# design.net
KiCad netlist of a schematic drawn in Altium Designer
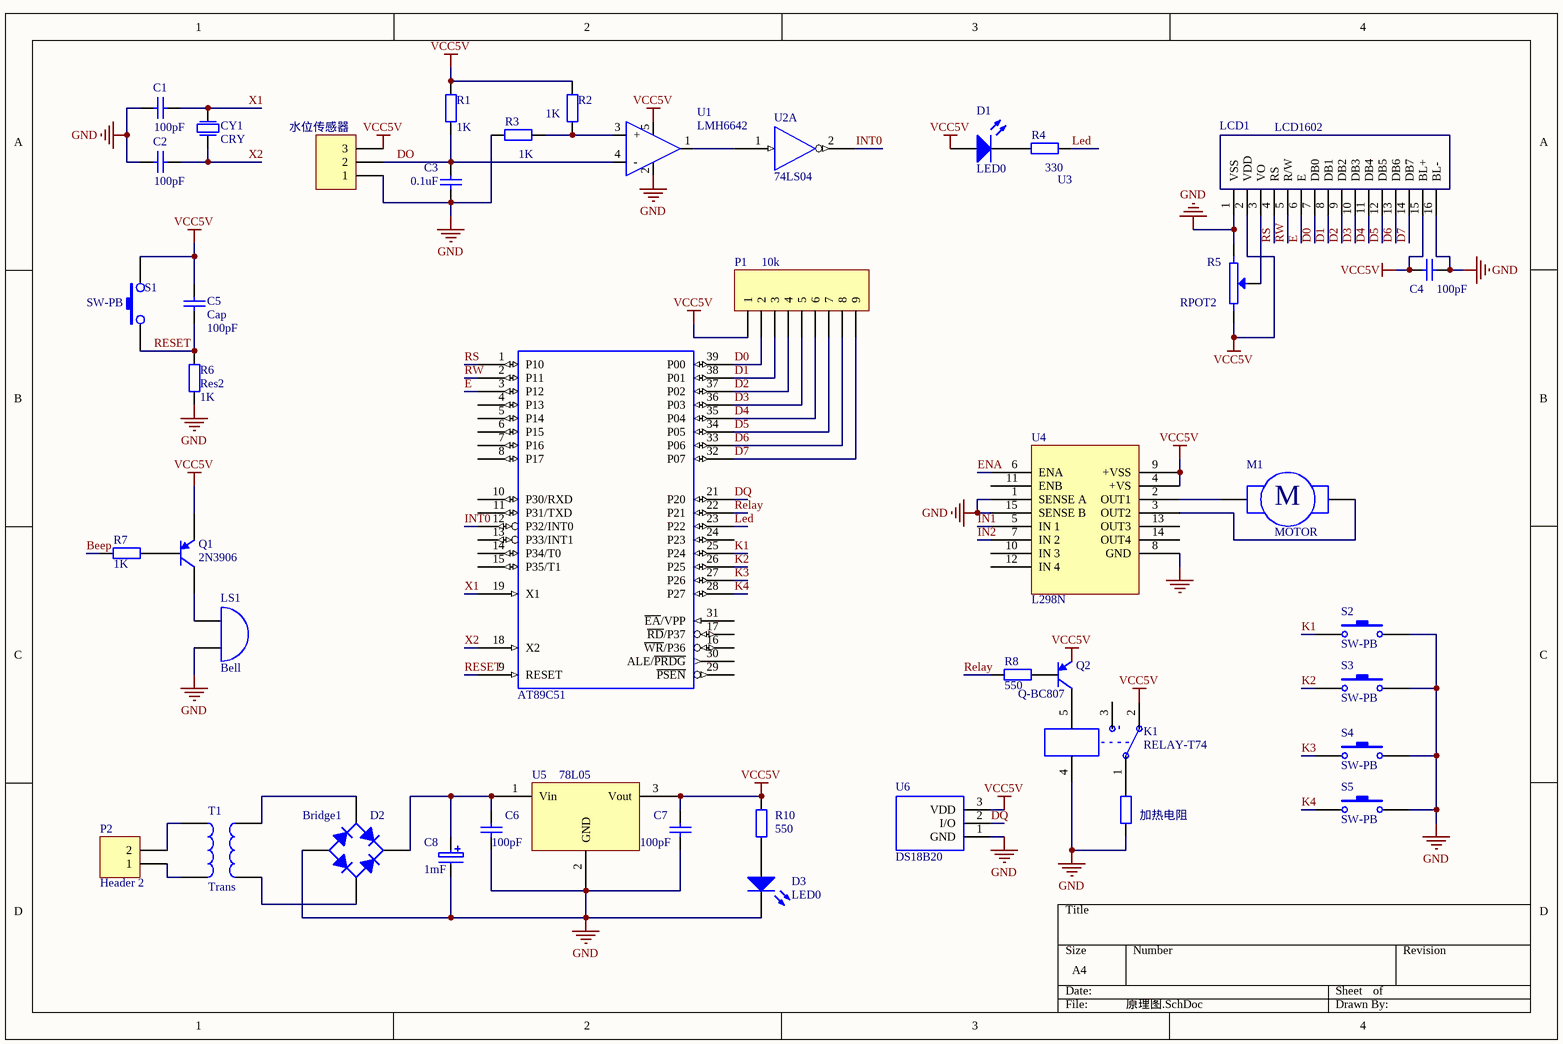
[diagram p0: 原理图.SchDoc]

(export (version "E")
  (design (tool "Eeschema 10.0.6"))
  (components
    (comp (ref "C1")
      (value "100pF")
      (footprint "RAD-0.3")
      (description "Capacitor")
      (fields (field (name "Comment") "Cap") (field (name "PUBLISHER") "Altium Limited"))
      (libsource (lib "Miscellaneous Devices") (part "Cap"))
    )
    (comp (ref "C2")
      (value "100pF")
      (footprint "RAD-0.3")
      (description "Capacitor")
      (fields (field (name "Comment") "Cap") (field (name "PUBLISHER") "Altium Limited"))
      (libsource (lib "Miscellaneous Devices") (part "Cap"))
    )
    (comp (ref "C3")
      (value "0.1uF")
      (footprint "RAD-0.3")
      (description "Capacitor")
      (fields (field (name "Comment") "Cap") (field (name "PUBLISHER") "Altium Limited"))
      (libsource (lib "Miscellaneous Devices") (part "Cap"))
    )
    (comp (ref "C4")
      (value "100pF")
      (footprint "RAD-0.3")
      (description "Capacitor")
      (fields (field (name "Comment") "Cap") (field (name "PUBLISHER") "Altium Limited"))
      (libsource (lib "Miscellaneous Devices") (part "Cap"))
    )
    (comp (ref "C5")
      (value "Cap")
      (footprint "RAD-0.3")
      (description "Capacitor")
      (fields (field (name "ALTIUM_VALUE") "100pF") (field (name "PUBLISHER") "Altium Limited"))
      (libsource (lib "Miscellaneous Devices") (part "Cap"))
    )
    (comp (ref "C6")
      (value "100pF")
      (footprint "RAD-0.3")
      (description "Capacitor")
      (fields (field (name "Comment") "Cap") (field (name "PUBLISHER") "Altium Limited"))
      (libsource (lib "Miscellaneous Devices") (part "Cap"))
    )
    (comp (ref "C7")
      (value "100pF")
      (footprint "RAD-0.3")
      (description "Capacitor")
      (fields (field (name "Comment") "Cap") (field (name "PUBLISHER") "Altium Limited"))
      (libsource (lib "Miscellaneous Devices") (part "Cap"))
    )
    (comp (ref "C8") (value "1mF") (footprint "RB1") (libsource (lib "C电容") (part "CAP3")))
    (comp (ref "CY1") (value "CRY") (footprint "XTAL-1") (libsource (lib "CRY晶振") (part "CRY")))
    (comp (ref "D1")
      (value "LED0")
      (footprint "LED-0")
      (description "Typical INFRARED GaAs LED")
      (fields (field (name "PUBLISHER") "Altium Limited"))
      (libsource (lib "Miscellaneous Devices") (part "LED0"))
    )
    (comp (ref "D2")
      (value "Bridge1")
      (footprint "D-38")
      (description "Full Wave Diode Bridge")
      (fields (field (name "PUBLISHER") "Altium Limited"))
      (libsource (lib "Miscellaneous Devices") (part "Bridge1"))
    )
    (comp (ref "D3")
      (value "LED0")
      (footprint "LED-0")
      (description "Typical INFRARED GaAs LED")
      (fields (field (name "PUBLISHER") "Altium Limited"))
      (libsource (lib "Miscellaneous Devices") (part "LED0"))
    )
    (comp (ref "K1")
      (value "RELAY-T74")
      (footprint "RELAY-T74")
      (description "CN-RELAY-T74")
      (libsource (lib "常用器件") (part "RELAY-T74"))
    )
    (comp (ref "LCD1") (value "LCD1602") (footprint "LCD1602") (libsource (lib "LCD1602") (part "LCD1602")))
    (comp (ref "LS1")
      (value "Bell")
      (footprint "PIN2")
      (description "Electrical Bell")
      (fields (field (name "PUBLISHER") "Altium Limited"))
      (libsource (lib "Miscellaneous Devices") (part "Bell"))
    )
    (comp (ref "M1") (value "MOTOR") (footprint "DG1282") (libsource (lib "单片机及相关") (part "MOTOR")))
    (comp (ref "P1")
      (value "10k")
      (footprint "MHDR1X9")
      (description "Header, 9-Pin")
      (fields (field (name "PUBLISHER") "Altium Limited"))
      (libsource (lib "Miscellaneous Connectors") (part "MHDR1X9"))
    )
    (comp (ref "P2")
      (value "Header 2")
      (footprint "HDR1X2")
      (description "Header, 2-Pin")
      (fields (field (name "PUBLISHER") "Altium Limited"))
      (libsource (lib "Miscellaneous Connectors") (part "Header 2"))
    )
    (comp (ref "Q1")
      (value "2N3906")
      (footprint "TO-92A")
      (description "PNP General Purpose Amplifier")
      (fields (field (name "PUBLISHER") "Altium Limited"))
      (libsource (lib "Miscellaneous Devices") (part "2N3906"))
    )
    (comp (ref "Q2")
      (value "Q-BC807")
      (footprint "SOT-23Q")
      (description "PNP General Purpose Amplifier")
      (fields (field (name "PUBLISHER") "Altium Limited"))
      (libsource (lib "常用器件") (part "Q-BC807"))
    )
    (comp (ref "R1")
      (value "1K")
      (footprint "AXIAL-0.4")
      (description "Resistor")
      (fields (field (name "Comment") "Res2") (field (name "PUBLISHER") "Altium Limited"))
      (libsource (lib "") (part "Res2_1"))
    )
    (comp (ref "R2")
      (value "1K")
      (footprint "AXIAL-0.4")
      (description "Resistor")
      (fields (field (name "Comment") "Res2") (field (name "PUBLISHER") "Altium Limited"))
      (libsource (lib "") (part "Res2_1"))
    )
    (comp (ref "R3")
      (value "1K")
      (footprint "AXIAL-0.4")
      (description "Resistor")
      (fields (field (name "Comment") "Res2") (field (name "PUBLISHER") "Altium Limited"))
      (libsource (lib "Miscellaneous Devices") (part "Res2"))
    )
    (comp (ref "R4")
      (value "330")
      (footprint "AXIAL-0.4")
      (description "Resistor")
      (fields (field (name "Comment") "Res2") (field (name "PUBLISHER") "Altium Limited"))
      (libsource (lib "Miscellaneous Devices") (part "Res2"))
    )
    (comp (ref "R5")
      (value "RPOT2")
      (footprint "VR5")
      (description "Potentiometer")
      (libsource (lib "电阻") (part "RPOT2"))
    )
    (comp (ref "R6")
      (value "Res2")
      (footprint "AXIAL-0.4")
      (description "Resistor")
      (fields (field (name "ALTIUM_VALUE") "1K") (field (name "PUBLISHER") "Altium Limited"))
      (libsource (lib "") (part "Res2_1"))
    )
    (comp (ref "R7")
      (value "1K")
      (footprint "AXIAL-0.4")
      (description "Resistor")
      (fields (field (name "Comment") "Res2") (field (name "PUBLISHER") "Altium Limited"))
      (libsource (lib "Miscellaneous Devices") (part "Res2"))
    )
    (comp (ref "R8")
      (value "550")
      (footprint "AXIAL-0.4")
      (description "Resistor")
      (fields (field (name "Comment") "Res2") (field (name "PUBLISHER") "Altium Limited"))
      (libsource (lib "Miscellaneous Devices") (part "Res2"))
    )
    (comp (ref "R10")
      (value "550")
      (footprint "AXIAL-0.4")
      (description "Resistor")
      (fields (field (name "Comment") "Res2") (field (name "PUBLISHER") "Altium Limited"))
      (libsource (lib "") (part "Res2_1"))
    )
    (comp (ref "S1") (value "SW-PB") (libsource (lib "SW开关") (part "SW-PB")))
    (comp (ref "S2")
      (value "SW-PB")
      (footprint "SPST-2")
      (description "Switch")
      (fields (field (name "PUBLISHER") "Altium Limited"))
      (libsource (lib "常用器件") (part "SW-PB"))
    )
    (comp (ref "S3")
      (value "SW-PB")
      (footprint "SPST-2")
      (description "Switch")
      (fields (field (name "PUBLISHER") "Altium Limited"))
      (libsource (lib "常用器件") (part "SW-PB"))
    )
    (comp (ref "S4")
      (value "SW-PB")
      (footprint "SPST-2")
      (description "Switch")
      (fields (field (name "PUBLISHER") "Altium Limited"))
      (libsource (lib "常用器件") (part "SW-PB"))
    )
    (comp (ref "S5")
      (value "SW-PB")
      (footprint "SPST-2")
      (description "Switch")
      (fields (field (name "PUBLISHER") "Altium Limited"))
      (libsource (lib "常用器件") (part "SW-PB"))
    )
    (comp (ref "T1")
      (value "Trans")
      (footprint "TRANS")
      (description "Transformer")
      (fields (field (name "PUBLISHER") "Altium Limited"))
      (libsource (lib "Miscellaneous Devices") (part "Trans"))
    )
    (comp (ref "U1") (value "LMH6642") (description "Amplifier IC") (libsource (lib "常用器件") (part "LMH6642")))
    (comp (ref "U2") (value "74LS04") (footprint "DIP-14") (libsource (lib "74xxTTL") (part "74LS04")))
    (comp (ref "U3") (value "AT89C51") (footprint "DIP-40") (libsource (lib "单片机及相关") (part "AT89C51")))
    (comp (ref "U4") (value "L298N") (footprint "L298N散热片") (libsource (lib "KU1") (part "L298N")))
    (comp (ref "U5") (value "78L05") (footprint "TO257V") (libsource (lib "稳压管") (part "78**")))
    (comp (ref "U6") (value "DS18B20") (footprint "TO-92A") (libsource (lib "单片机及相关") (part "DS18B20")))
    (comp (ref "加热电阻")
      (value "Res2")
      (footprint "AXIAL-0.4")
      (description "Resistor")
      (fields (field (name "PUBLISHER") "Altium Limited"))
      (libsource (lib "") (part "Res2_1"))
    )
    (comp (ref "水位传感器")
      (value "Header 3H")
      (footprint "HDR1X3H")
      (description "Header, 3-Pin, Right Angle")
      (fields (field (name "PUBLISHER") "Altium Limited"))
      (libsource (lib "Miscellaneous Connectors") (part "Header 3H"))
    )
  )
  (nets
    (net (code "1") (name "/Beep") (class "Default")
      (node (ref "R7") (pin "2") (pinfunction "2_2") (pintype "passive"))
    )
    (net (code "2") (name "/D0") (class "Default")
      (node (ref "LCD1") (pin "7") (pinfunction "DB0_7") (pintype "passive"))
      (node (ref "P1") (pin "2") (pinfunction "2_2") (pintype "passive"))
      (node (ref "U3") (pin "39") (pinfunction "P00_39") (pintype "bidirectional"))
    )
    (net (code "3") (name "/D1") (class "Default")
      (node (ref "LCD1") (pin "8") (pinfunction "DB1_8") (pintype "passive"))
      (node (ref "P1") (pin "3") (pinfunction "3_3") (pintype "passive"))
      (node (ref "U3") (pin "38") (pinfunction "P01_38") (pintype "bidirectional"))
    )
    (net (code "4") (name "/D2") (class "Default")
      (node (ref "LCD1") (pin "9") (pinfunction "DB2_9") (pintype "passive"))
      (node (ref "P1") (pin "4") (pinfunction "4_4") (pintype "passive"))
      (node (ref "U3") (pin "37") (pinfunction "P02_37") (pintype "bidirectional"))
    )
    (net (code "5") (name "/D3") (class "Default")
      (node (ref "LCD1") (pin "10") (pinfunction "DB3_10") (pintype "passive"))
      (node (ref "P1") (pin "5") (pinfunction "5_5") (pintype "passive"))
      (node (ref "U3") (pin "36") (pinfunction "P03_36") (pintype "bidirectional"))
    )
    (net (code "6") (name "/D4") (class "Default")
      (node (ref "LCD1") (pin "11") (pinfunction "DB4_11") (pintype "passive"))
      (node (ref "P1") (pin "6") (pinfunction "6_6") (pintype "passive"))
      (node (ref "U3") (pin "35") (pinfunction "P04_35") (pintype "bidirectional"))
    )
    (net (code "7") (name "/D5") (class "Default")
      (node (ref "LCD1") (pin "12") (pinfunction "DB5_12") (pintype "passive"))
      (node (ref "P1") (pin "7") (pinfunction "7_7") (pintype "passive"))
      (node (ref "U3") (pin "34") (pinfunction "P05_34") (pintype "bidirectional"))
    )
    (net (code "8") (name "/D6") (class "Default")
      (node (ref "LCD1") (pin "13") (pinfunction "DB6_13") (pintype "passive"))
      (node (ref "P1") (pin "8") (pinfunction "8_8") (pintype "passive"))
      (node (ref "U3") (pin "33") (pinfunction "P06_33") (pintype "bidirectional"))
    )
    (net (code "9") (name "/D7") (class "Default")
      (node (ref "LCD1") (pin "14") (pinfunction "DB7_14") (pintype "passive"))
      (node (ref "P1") (pin "9") (pinfunction "9_9") (pintype "passive"))
      (node (ref "U3") (pin "32") (pinfunction "P07_32") (pintype "bidirectional"))
    )
    (net (code "10") (name "/DO") (class "Default")
      (node (ref "C3") (pin "2") (pinfunction "2_2") (pintype "passive"))
      (node (ref "R1") (pin "1") (pinfunction "1_1") (pintype "passive"))
      (node (ref "U1") (pin "4") (pinfunction "-_4") (pintype "passive"))
      (node (ref "水位传感器") (pin "2") (pinfunction "2_2") (pintype "passive"))
    )
    (net (code "11") (name "/DQ") (class "Default")
      (node (ref "U3") (pin "21") (pinfunction "P20_21") (pintype "bidirectional"))
      (node (ref "U6") (pin "2") (pinfunction "I/O_2") (pintype "passive"))
    )
    (net (code "12") (name "/E") (class "Default")
      (node (ref "LCD1") (pin "6") (pinfunction "E_6") (pintype "passive"))
      (node (ref "U3") (pin "3") (pinfunction "P12_3") (pintype "bidirectional"))
    )
    (net (code "13") (name "/ENA") (class "Default")
      (node (ref "U4") (pin "6") (pinfunction "ENA_6") (pintype "passive"))
    )
    (net (code "14") (name "/IN1") (class "Default")
      (node (ref "U4") (pin "5") (pinfunction "IN_1_5") (pintype "passive"))
    )
    (net (code "15") (name "/IN2") (class "Default")
      (node (ref "U4") (pin "7") (pinfunction "IN_2_7") (pintype "passive"))
    )
    (net (code "16") (name "/INT0") (class "Default")
      (node (ref "U2") (pin "2") (pintype "output"))
      (node (ref "U3") (pin "12") (pinfunction "P32/INT0_12") (pintype "bidirectional"))
    )
    (net (code "17") (name "/K1") (class "Default")
      (node (ref "S2") (pin "1") (pinfunction "1_1") (pintype "passive"))
      (node (ref "U3") (pin "25") (pinfunction "P24_25") (pintype "bidirectional"))
    )
    (net (code "18") (name "/K2") (class "Default")
      (node (ref "S3") (pin "1") (pinfunction "1_1") (pintype "passive"))
      (node (ref "U3") (pin "26") (pinfunction "P25_26") (pintype "bidirectional"))
    )
    (net (code "19") (name "/K3") (class "Default")
      (node (ref "S4") (pin "1") (pinfunction "1_1") (pintype "passive"))
      (node (ref "U3") (pin "27") (pinfunction "P26_27") (pintype "bidirectional"))
    )
    (net (code "20") (name "/K4") (class "Default")
      (node (ref "S5") (pin "1") (pinfunction "1_1") (pintype "passive"))
      (node (ref "U3") (pin "28") (pinfunction "P27_28") (pintype "bidirectional"))
    )
    (net (code "21") (name "/Led") (class "Default")
      (node (ref "R4") (pin "1") (pinfunction "1_1") (pintype "passive"))
      (node (ref "U3") (pin "23") (pinfunction "P22_23") (pintype "bidirectional"))
    )
    (net (code "22") (name "/RESET") (class "Default")
      (node (ref "C5") (pin "1") (pinfunction "1_1") (pintype "passive"))
      (node (ref "R6") (pin "2") (pinfunction "2_2") (pintype "passive"))
      (node (ref "S1") (pin "1") (pinfunction "1_1") (pintype "passive"))
      (node (ref "U3") (pin "9") (pinfunction "RESET_9") (pintype "input"))
    )
    (net (code "23") (name "/RS") (class "Default")
      (node (ref "LCD1") (pin "4") (pinfunction "RS_4") (pintype "passive"))
      (node (ref "U3") (pin "1") (pinfunction "P10_1") (pintype "bidirectional"))
    )
    (net (code "24") (name "/RW") (class "Default")
      (node (ref "LCD1") (pin "5") (pinfunction "R/W_5") (pintype "passive"))
      (node (ref "U3") (pin "2") (pinfunction "P11_2") (pintype "bidirectional"))
    )
    (net (code "25") (name "/Relay") (class "Default")
      (node (ref "R8") (pin "2") (pinfunction "2_2") (pintype "passive"))
      (node (ref "U3") (pin "22") (pinfunction "P21_22") (pintype "bidirectional"))
    )
    (net (code "26") (name "/X1") (class "Default")
      (node (ref "C1") (pin "2") (pinfunction "2_2") (pintype "passive"))
      (node (ref "CY1") (pin "1") (pinfunction "P1_1") (pintype "passive"))
      (node (ref "U3") (pin "19") (pinfunction "X1_19") (pintype "input"))
    )
    (net (code "27") (name "/X2") (class "Default")
      (node (ref "C2") (pin "2") (pinfunction "2_2") (pintype "passive"))
      (node (ref "CY1") (pin "2") (pinfunction "P2_2") (pintype "passive"))
      (node (ref "U3") (pin "18") (pinfunction "X2_18") (pintype "input"))
    )
    (net (code "28") (name "GND") (class "Default")
      (node (ref "C1") (pin "1") (pinfunction "1_1") (pintype "passive"))
      (node (ref "C2") (pin "1") (pinfunction "1_1") (pintype "passive"))
      (node (ref "C3") (pin "1") (pinfunction "1_1") (pintype "passive"))
      (node (ref "C4") (pin "1") (pinfunction "1_1") (pintype "passive"))
      (node (ref "C6") (pin "1") (pinfunction "1_1") (pintype "passive"))
      (node (ref "C7") (pin "1") (pinfunction "1_1") (pintype "passive"))
      (node (ref "C8") (pin "2") (pintype "passive"))
      (node (ref "D2") (pin "3") (pinfunction "A_3") (pintype "passive"))
      (node (ref "D3") (pin "2") (pinfunction "K_2") (pintype "passive"))
      (node (ref "K1") (pin "4") (pinfunction "4_4") (pintype "passive"))
      (node (ref "LCD1") (pin "1") (pinfunction "VSS_1") (pintype "passive"))
      (node (ref "LCD1") (pin "16") (pinfunction "BL-_16") (pintype "passive"))
      (node (ref "LS1") (pin "2") (pinfunction "B_2") (pintype "passive"))
      (node (ref "R3") (pin "2") (pinfunction "2_2") (pintype "passive"))
      (node (ref "R5") (pin "3") (pinfunction "2_3") (pintype "passive"))
      (node (ref "R6") (pin "1") (pinfunction "1_1") (pintype "passive"))
      (node (ref "S2") (pin "2") (pinfunction "2_2") (pintype "passive"))
      (node (ref "S3") (pin "2") (pinfunction "2_2") (pintype "passive"))
      (node (ref "S4") (pin "2") (pinfunction "2_2") (pintype "passive"))
      (node (ref "S5") (pin "2") (pinfunction "2_2") (pintype "passive"))
      (node (ref "U1") (pin "2") (pinfunction "V-_2") (pintype "passive"))
      (node (ref "U2") (pin "7") (pinfunction "GND_7") (pintype "power_in"))
      (node (ref "U3") (pin "20") (pinfunction "GND_20") (pintype "power_in"))
      (node (ref "U4") (pin "1") (pinfunction "SENSE_A_1") (pintype "passive"))
      (node (ref "U4") (pin "15") (pinfunction "SENSE_B_15") (pintype "passive"))
      (node (ref "U4") (pin "8") (pinfunction "GND_8") (pintype "passive"))
      (node (ref "U5") (pin "2") (pinfunction "GND_2") (pintype "passive"))
      (node (ref "U6") (pin "1") (pinfunction "GND_1") (pintype "passive"))
      (node (ref "加热电阻") (pin "1") (pinfunction "1_1") (pintype "passive"))
      (node (ref "水位传感器") (pin "1") (pinfunction "1_1") (pintype "passive"))
    )
    (net (code "29") (name "Net-(D1-K)") (class "Default")
      (node (ref "D1") (pin "2") (pinfunction "K_2") (pintype "passive"))
      (node (ref "R4") (pin "2") (pinfunction "2_2") (pintype "passive"))
    )
    (net (code "30") (name "Net-(D2-C-Pad2)") (class "Default")
      (node (ref "D2") (pin "2") (pinfunction "C_2") (pintype "passive"))
      (node (ref "T1") (pin "4") (pinfunction "4_4") (pintype "passive"))
    )
    (net (code "31") (name "Net-(D2-C-Pad4)") (class "Default")
      (node (ref "D2") (pin "4") (pinfunction "C_4") (pintype "passive"))
      (node (ref "T1") (pin "3") (pinfunction "3_3") (pintype "passive"))
    )
    (net (code "32") (name "Net-(D2-K)") (class "Default")
      (node (ref "C6") (pin "2") (pinfunction "2_2") (pintype "passive"))
      (node (ref "C8") (pin "1") (pintype "passive"))
      (node (ref "D2") (pin "1") (pinfunction "K_1") (pintype "passive"))
      (node (ref "U5") (pin "1") (pinfunction "Vin_1") (pintype "passive"))
    )
    (net (code "33") (name "Net-(D3-A)") (class "Default")
      (node (ref "D3") (pin "1") (pinfunction "A_1") (pintype "passive"))
      (node (ref "R10") (pin "1") (pinfunction "1_1") (pintype "passive"))
    )
    (net (code "34") (name "Net-(K1-Pad1)") (class "Default")
      (node (ref "K1") (pin "1") (pinfunction "1_1") (pintype "passive"))
      (node (ref "加热电阻") (pin "2") (pinfunction "2_2") (pintype "passive"))
    )
    (net (code "35") (name "Net-(K1-Pad5)") (class "Default")
      (node (ref "K1") (pin "5") (pinfunction "5_5") (pintype "passive"))
      (node (ref "Q2") (pin "C") (pinfunction "C_C") (pintype "passive"))
    )
    (net (code "36") (name "Net-(LCD1-VO)") (class "Default")
      (node (ref "LCD1") (pin "3") (pinfunction "VO_3") (pintype "passive"))
      (node (ref "R5") (pin "2") (pinfunction "VT_2") (pintype "passive"))
    )
    (net (code "37") (name "Net-(LS1-A)") (class "Default")
      (node (ref "LS1") (pin "1") (pinfunction "A_1") (pintype "passive"))
      (node (ref "Q1") (pin "3") (pinfunction "C_3") (pintype "passive"))
    )
    (net (code "38") (name "Net-(P2-Pad1)") (class "Default")
      (node (ref "P2") (pin "1") (pinfunction "1_1") (pintype "passive"))
      (node (ref "T1") (pin "2") (pinfunction "2_2") (pintype "passive"))
    )
    (net (code "39") (name "Net-(P2-Pad2)") (class "Default")
      (node (ref "P2") (pin "2") (pinfunction "2_2") (pintype "passive"))
      (node (ref "T1") (pin "1") (pinfunction "1_1") (pintype "passive"))
    )
    (net (code "40") (name "Net-(Q1-B)") (class "Default")
      (node (ref "Q1") (pin "2") (pinfunction "B_2") (pintype "passive"))
      (node (ref "R7") (pin "1") (pinfunction "1_1") (pintype "passive"))
    )
    (net (code "41") (name "Net-(Q2-PadB)") (class "Default")
      (node (ref "Q2") (pin "B") (pinfunction "B_B") (pintype "passive"))
      (node (ref "R8") (pin "1") (pinfunction "1_1") (pintype "passive"))
    )
    (net (code "42") (name "Net-(U1-+)") (class "Default")
      (node (ref "R2") (pin "1") (pinfunction "1_1") (pintype "passive"))
      (node (ref "R3") (pin "1") (pinfunction "1_1") (pintype "passive"))
      (node (ref "U1") (pin "3") (pinfunction "+_3") (pintype "passive"))
    )
    (net (code "43") (name "Net-(U1-OUT)") (class "Default")
      (node (ref "U1") (pin "1") (pinfunction "OUT_1") (pintype "passive"))
      (node (ref "U2") (pin "1") (pintype "input"))
    )
    (net (code "44") (name "Net-(U4-OUT1)") (class "Default")
      (node (ref "M1") (pin "2") (pinfunction "2_2") (pintype "passive"))
      (node (ref "U4") (pin "2") (pinfunction "OUT1_2") (pintype "passive"))
    )
    (net (code "45") (name "Net-(U4-OUT2)") (class "Default")
      (node (ref "M1") (pin "1") (pinfunction "1_1") (pintype "passive"))
      (node (ref "U4") (pin "3") (pinfunction "OUT2_3") (pintype "passive"))
    )
    (net (code "46") (name "VCC") (class "Default")
      (node (ref "U2") (pin "14") (pinfunction "VCC_14") (pintype "power_in"))
      (node (ref "U3") (pin "40") (pinfunction "VCC_40") (pintype "power_in"))
    )
    (net (code "47") (name "VCC5V") (class "Default")
      (node (ref "C4") (pin "2") (pinfunction "2_2") (pintype "passive"))
      (node (ref "C5") (pin "2") (pinfunction "2_2") (pintype "passive"))
      (node (ref "C7") (pin "2") (pinfunction "2_2") (pintype "passive"))
      (node (ref "D1") (pin "1") (pinfunction "A_1") (pintype "passive"))
      (node (ref "K1") (pin "2") (pinfunction "2_2") (pintype "passive"))
      (node (ref "LCD1") (pin "15") (pinfunction "BL+_15") (pintype "passive"))
      (node (ref "LCD1") (pin "2") (pinfunction "VDD_2") (pintype "passive"))
      (node (ref "P1") (pin "1") (pinfunction "1_1") (pintype "passive"))
      (node (ref "Q1") (pin "1") (pinfunction "E_1") (pintype "passive"))
      (node (ref "R1") (pin "2") (pinfunction "2_2") (pintype "passive"))
      (node (ref "R10") (pin "2") (pinfunction "2_2") (pintype "passive"))
      (node (ref "R2") (pin "2") (pinfunction "2_2") (pintype "passive"))
      (node (ref "R5") (pin "1") (pinfunction "1_1") (pintype "passive"))
      (node (ref "S1") (pin "2") (pinfunction "2_2") (pintype "passive"))
      (node (ref "U1") (pin "5") (pinfunction "V+_5") (pintype "passive"))
      (node (ref "U4") (pin "4") (pinfunction "+VS_4") (pintype "passive"))
      (node (ref "U4") (pin "9") (pinfunction "+VSS_9") (pintype "passive"))
      (node (ref "U5") (pin "3") (pinfunction "Vout_3") (pintype "passive"))
      (node (ref "U6") (pin "3") (pinfunction "VDD_3") (pintype "passive"))
      (node (ref "水位传感器") (pin "3") (pinfunction "3_3") (pintype "passive"))
    )
    (net (code "48") (name "unconnected-(K1-Pad3)") (class "Default")
      (node (ref "K1") (pin "3") (pinfunction "3_3") (pintype "passive"))
    )
    (net (code "49") (name "unconnected-(Q2-PadE)") (class "Default")
      (node (ref "Q2") (pin "E") (pinfunction "E_E") (pintype "passive"))
    )
    (net (code "50") (name "unconnected-(U3-ALE{slash}~{PRDG}-Pad30)") (class "Default")
      (node (ref "U3") (pin "30") (pinfunction "ALE/~{PRDG}_30") (pintype "output"))
    )
    (net (code "51") (name "unconnected-(U3-P13-Pad4)") (class "Default")
      (node (ref "U3") (pin "4") (pinfunction "P13_4") (pintype "bidirectional"))
    )
    (net (code "52") (name "unconnected-(U3-P14-Pad5)") (class "Default")
      (node (ref "U3") (pin "5") (pinfunction "P14_5") (pintype "bidirectional"))
    )
    (net (code "53") (name "unconnected-(U3-P15-Pad6)") (class "Default")
      (node (ref "U3") (pin "6") (pinfunction "P15_6") (pintype "bidirectional"))
    )
    (net (code "54") (name "unconnected-(U3-P16-Pad7)") (class "Default")
      (node (ref "U3") (pin "7") (pinfunction "P16_7") (pintype "bidirectional"))
    )
    (net (code "55") (name "unconnected-(U3-P17-Pad8)") (class "Default")
      (node (ref "U3") (pin "8") (pinfunction "P17_8") (pintype "bidirectional"))
    )
    (net (code "56") (name "unconnected-(U3-P23-Pad24)") (class "Default")
      (node (ref "U3") (pin "24") (pinfunction "P23_24") (pintype "bidirectional"))
    )
    (net (code "57") (name "unconnected-(U3-P30{slash}RXD-Pad10)") (class "Default")
      (node (ref "U3") (pin "10") (pinfunction "P30/RXD_10") (pintype "bidirectional"))
    )
    (net (code "58") (name "unconnected-(U3-P31{slash}TXD-Pad11)") (class "Default")
      (node (ref "U3") (pin "11") (pinfunction "P31/TXD_11") (pintype "bidirectional"))
    )
    (net (code "59") (name "unconnected-(U3-P33{slash}INT1-Pad13)") (class "Default")
      (node (ref "U3") (pin "13") (pinfunction "P33/INT1_13") (pintype "bidirectional"))
    )
    (net (code "60") (name "unconnected-(U3-P34{slash}T0-Pad14)") (class "Default")
      (node (ref "U3") (pin "14") (pinfunction "P34/T0_14") (pintype "bidirectional"))
    )
    (net (code "61") (name "unconnected-(U3-P35{slash}T1-Pad15)") (class "Default")
      (node (ref "U3") (pin "15") (pinfunction "P35/T1_15") (pintype "bidirectional"))
    )
    (net (code "62") (name "unconnected-(U3-~{EA}{slash}VPP-Pad31)") (class "Default")
      (node (ref "U3") (pin "31") (pinfunction "~{EA}/VPP_31") (pintype "input"))
    )
    (net (code "63") (name "unconnected-(U3-~{PSEN}-Pad29)") (class "Default")
      (node (ref "U3") (pin "29") (pinfunction "~{PSEN}_29") (pintype "output"))
    )
    (net (code "64") (name "unconnected-(U3-~{RD}{slash}P37-Pad17)") (class "Default")
      (node (ref "U3") (pin "17") (pinfunction "~{RD}/P37_17") (pintype "bidirectional"))
    )
    (net (code "65") (name "unconnected-(U3-~{WR}{slash}P36-Pad16)") (class "Default")
      (node (ref "U3") (pin "16") (pinfunction "~{WR}/P36_16") (pintype "bidirectional"))
    )
    (net (code "66") (name "unconnected-(U4-ENB-Pad11)") (class "Default")
      (node (ref "U4") (pin "11") (pinfunction "ENB_11") (pintype "passive"))
    )
    (net (code "67") (name "unconnected-(U4-IN_3-Pad10)") (class "Default")
      (node (ref "U4") (pin "10") (pinfunction "IN_3_10") (pintype "passive"))
    )
    (net (code "68") (name "unconnected-(U4-IN_4-Pad12)") (class "Default")
      (node (ref "U4") (pin "12") (pinfunction "IN_4_12") (pintype "passive"))
    )
    (net (code "69") (name "unconnected-(U4-OUT3-Pad13)") (class "Default")
      (node (ref "U4") (pin "13") (pinfunction "OUT3_13") (pintype "passive"))
    )
    (net (code "70") (name "unconnected-(U4-OUT4-Pad14)") (class "Default")
      (node (ref "U4") (pin "14") (pinfunction "OUT4_14") (pintype "passive"))
    )
  )
)
